# CH340C.net
KiCad netlist of a schematic drawn in Altium Designer
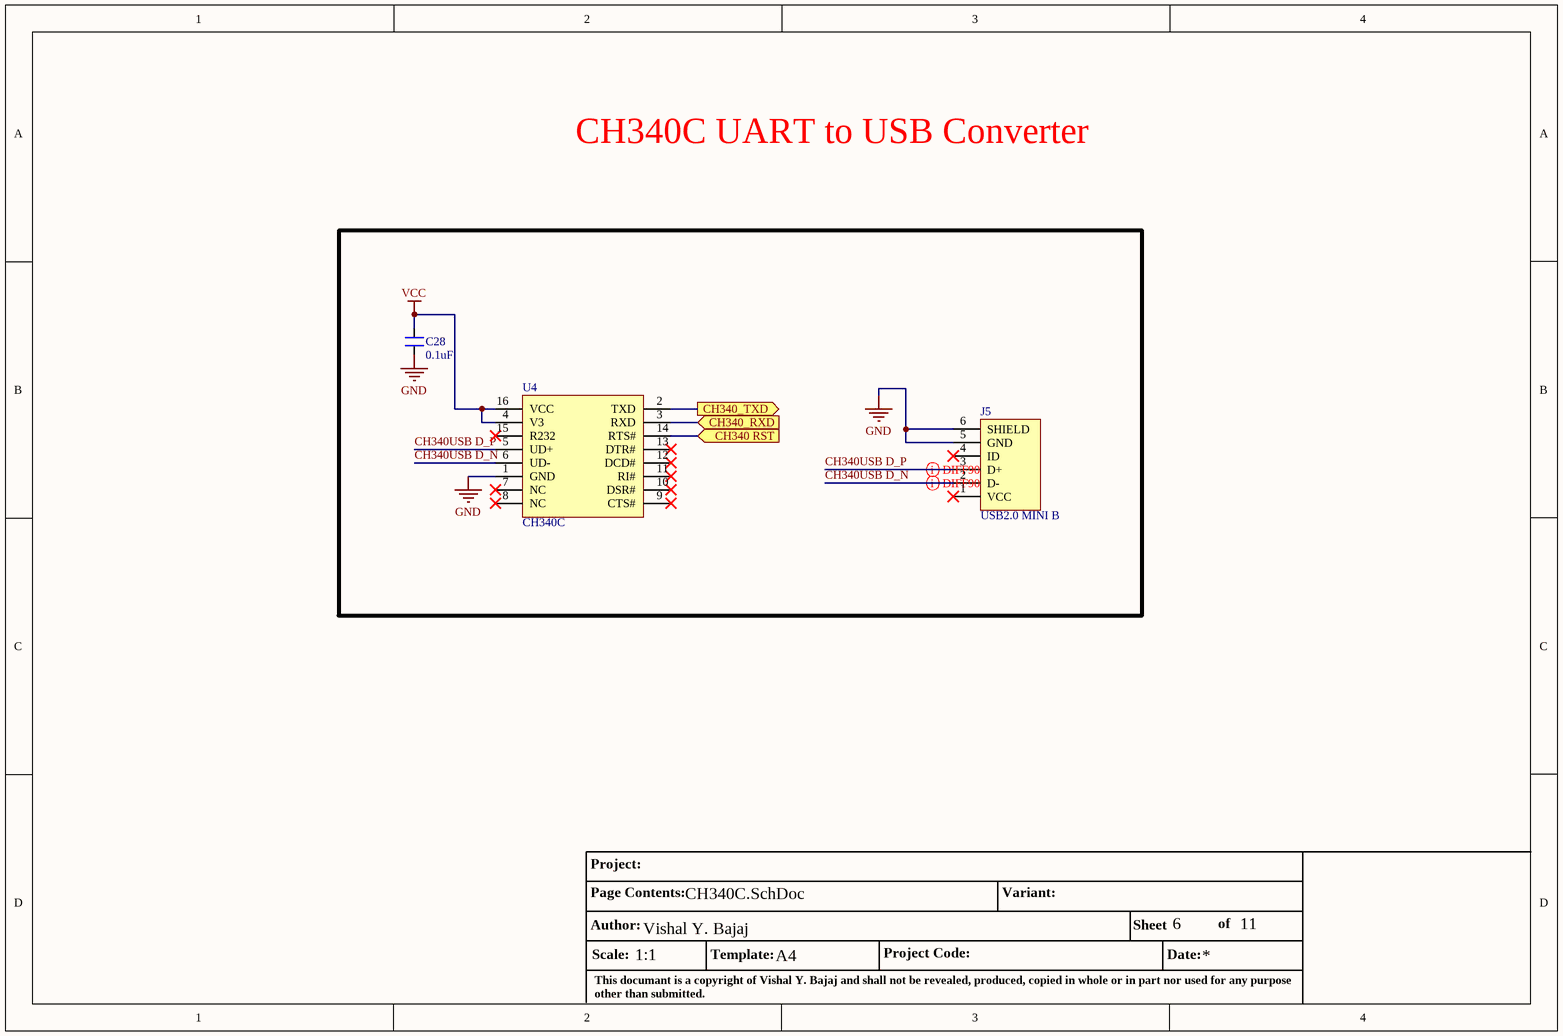
[diagram p0: CH340C.SchDoc]

(export (version "E")
  (design (tool "Eeschema 10.0.6"))
  (components
    (comp (ref "C28")
      (value "0.1uF")
      (footprint "CAP_0805")
      (description "0.1µF ±10% 50V Ceramic Capacitor X7R 0805 (2012 Metric)")
      (fields
        (field (name "MANUFACTURER") "Samsung")
        (field (name "MANUFACTURER PART NUMBER") "CL21B104KBCNNNC")
      )
      (libsource (lib "ESTEEMPCBLIB") (part "CAP_0.1uF-50V-10%-0805"))
    )
    (comp (ref "J5")
      (value "USB2.0 MINI B")
      (footprint "CON_690-005-299-043")
      (description "USB - mini B USB 2.0 Receptacle Connector 5 Position Surface Mount, Right Angle")
      (fields
        (field (name "MANUFACTURER") "EDAC")
        (field (name "MANUFACTURER PART NUMBER") "690-005-299-043")
      )
      (libsource (lib "ESTEEMPCBLIB") (part "CON_USB2.0-MINIB-SMD"))
    )
    (comp (ref "U4")
      (value "CH340C")
      (footprint "SOIC16_50_284_25X90_SMT")
      (description "USB Bridge, USB to UART USB 2.0 UART Interface")
      (fields (field (name "MANUFACTURER") "Olimex"))
      (libsource (lib "ESTEEMPCBLIB") (part "IC_CH340C"))
    )
  )
  (nets
    (net (code "2") (name "/CH340 RST") (class "Default")
      (node (ref "U4") (pin "14") (pinfunction "RTS#_14") (pintype "passive"))
    )
    (net (code "3") (name "/CH340USB D_N") (class "Default")
      (node (ref "J5") (pin "2") (pinfunction "D-_2") (pintype "passive"))
      (node (ref "U4") (pin "6") (pinfunction "UD-_6") (pintype "passive"))
    )
    (net (code "4") (name "/CH340USB D_P") (class "Default")
      (node (ref "J5") (pin "3") (pinfunction "D+_3") (pintype "passive"))
      (node (ref "U4") (pin "5") (pinfunction "UD+_5") (pintype "passive"))
    )
    (net (code "5") (name "/CH340_RXD") (class "Default")
      (node (ref "U4") (pin "3") (pinfunction "RXD_3") (pintype "passive"))
    )
    (net (code "6") (name "/CH340_TXD") (class "Default")
      (node (ref "U4") (pin "2") (pinfunction "TXD_2") (pintype "passive"))
    )
    (net (code "7") (name "GND") (class "Default")
      (node (ref "C28") (pin "1") (pinfunction "1_1") (pintype "passive"))
      (node (ref "J5") (pin "5") (pinfunction "GND_5") (pintype "passive"))
      (node (ref "J5") (pin "6") (pinfunction "SHIELD_6") (pintype "passive"))
      (node (ref "U4") (pin "1") (pinfunction "GND_1") (pintype "passive"))
    )
    (net (code "8") (name "VCC") (class "Default")
      (node (ref "C28") (pin "2") (pinfunction "2_2") (pintype "passive"))
      (node (ref "U4") (pin "16") (pinfunction "VCC_16") (pintype "passive"))
      (node (ref "U4") (pin "4") (pinfunction "V3_4") (pintype "passive"))
    )
    (net (code "9") (name "unconnected-(J5-ID-Pad4)") (class "Default")
      (node (ref "J5") (pin "4") (pinfunction "ID_4") (pintype "passive+no_connect"))
    )
    (net (code "10") (name "unconnected-(J5-VCC-Pad1)") (class "Default")
      (node (ref "J5") (pin "1") (pinfunction "VCC_1") (pintype "passive+no_connect"))
    )
    (net (code "11") (name "unconnected-(U4-CTS#-Pad9)") (class "Default")
      (node (ref "U4") (pin "9") (pinfunction "CTS#_9") (pintype "passive+no_connect"))
    )
    (net (code "12") (name "unconnected-(U4-DCD#-Pad12)") (class "Default")
      (node (ref "U4") (pin "12") (pinfunction "DCD#_12") (pintype "passive+no_connect"))
    )
    (net (code "13") (name "unconnected-(U4-DSR#-Pad10)") (class "Default")
      (node (ref "U4") (pin "10") (pinfunction "DSR#_10") (pintype "passive+no_connect"))
    )
    (net (code "14") (name "unconnected-(U4-DTR#-Pad13)") (class "Default")
      (node (ref "U4") (pin "13") (pinfunction "DTR#_13") (pintype "passive+no_connect"))
    )
    (net (code "15") (name "unconnected-(U4-NC-Pad7)") (class "Default")
      (node (ref "U4") (pin "7") (pinfunction "NC_7") (pintype "passive+no_connect"))
    )
    (net (code "16") (name "unconnected-(U4-NC-Pad8)") (class "Default")
      (node (ref "U4") (pin "8") (pinfunction "NC_8") (pintype "passive+no_connect"))
    )
    (net (code "17") (name "unconnected-(U4-R232-Pad15)") (class "Default")
      (node (ref "U4") (pin "15") (pinfunction "R232_15") (pintype "passive+no_connect"))
    )
    (net (code "18") (name "unconnected-(U4-RI#-Pad11)") (class "Default")
      (node (ref "U4") (pin "11") (pinfunction "RI#_11") (pintype "passive+no_connect"))
    )
  )
)
